# 8_U-FL-Connectors_no_GND.net
KiCad netlist of a schematic drawn in Altium Designer
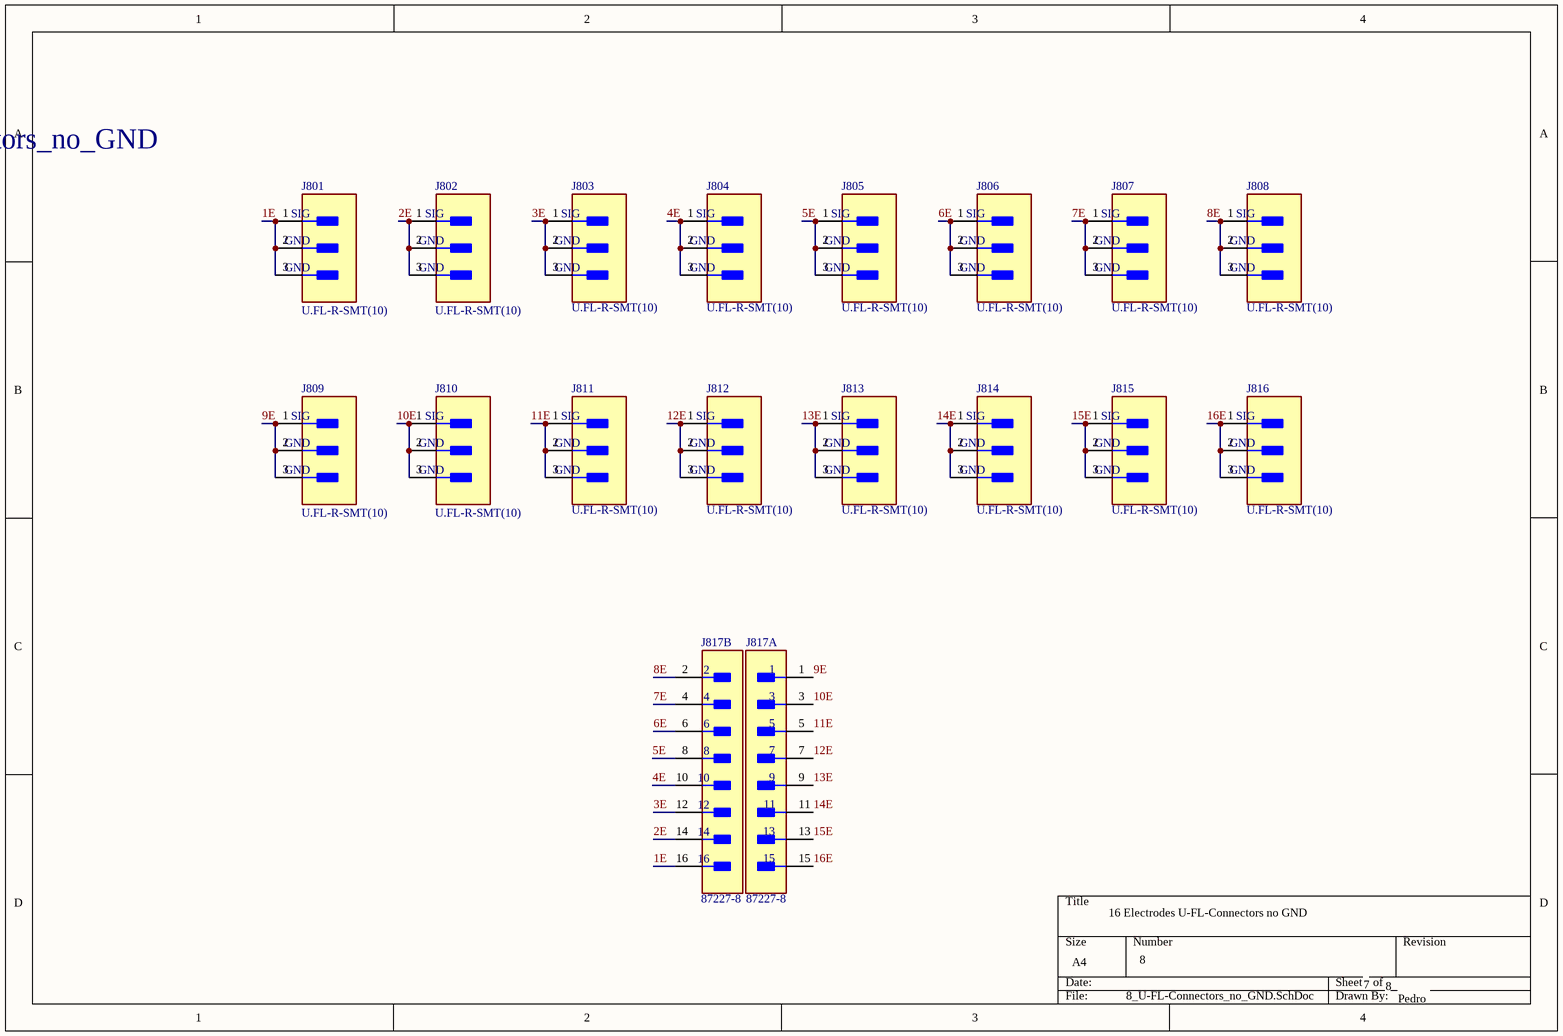
[diagram p0: 8_U-FL-Connectors_no_GND.SchDoc]

(export (version "E")
  (design (tool "Eeschema 10.0.6"))
  (components
    (comp (ref "J801")
      (value "U.FL-R-SMT(10)")
      (footprint "FP-U_FL-R-SMT_10-MFG")
      (description "CONN U.FL RCPT STR 50 OHM SMD")
      (libsource (lib "RPI_EIT_SchLib") (part "eef6fde44c591823e8076210edfe12f"))
    )
    (comp (ref "J802")
      (value "U.FL-R-SMT(10)")
      (footprint "FP-U_FL-R-SMT_10-MFG")
      (description "CONN U.FL RCPT STR 50 OHM SMD")
      (libsource (lib "RPI_EIT_SchLib") (part "eef6fde44c591823e8076210edfe12f"))
    )
    (comp (ref "J803")
      (value "U.FL-R-SMT(10)")
      (footprint "FP-U_FL-R-SMT_10-MFG")
      (description "CONN U.FL RCPT STR 50 OHM SMD")
      (libsource (lib "RPI_EIT_SchLib") (part "eef6fde44c591823e8076210edfe12f"))
    )
    (comp (ref "J804")
      (value "U.FL-R-SMT(10)")
      (footprint "FP-U_FL-R-SMT_10-MFG")
      (description "CONN U.FL RCPT STR 50 OHM SMD")
      (libsource (lib "RPI_EIT_SchLib") (part "eef6fde44c591823e8076210edfe12f"))
    )
    (comp (ref "J805")
      (value "U.FL-R-SMT(10)")
      (footprint "FP-U_FL-R-SMT_10-MFG")
      (description "CONN U.FL RCPT STR 50 OHM SMD")
      (libsource (lib "RPI_EIT_SchLib") (part "eef6fde44c591823e8076210edfe12f"))
    )
    (comp (ref "J806")
      (value "U.FL-R-SMT(10)")
      (footprint "FP-U_FL-R-SMT_10-MFG")
      (description "CONN U.FL RCPT STR 50 OHM SMD")
      (libsource (lib "RPI_EIT_SchLib") (part "eef6fde44c591823e8076210edfe12f"))
    )
    (comp (ref "J807")
      (value "U.FL-R-SMT(10)")
      (footprint "FP-U_FL-R-SMT_10-MFG")
      (description "CONN U.FL RCPT STR 50 OHM SMD")
      (libsource (lib "RPI_EIT_SchLib") (part "eef6fde44c591823e8076210edfe12f"))
    )
    (comp (ref "J808")
      (value "U.FL-R-SMT(10)")
      (footprint "FP-U_FL-R-SMT_10-MFG")
      (description "CONN U.FL RCPT STR 50 OHM SMD")
      (libsource (lib "RPI_EIT_SchLib") (part "eef6fde44c591823e8076210edfe12f"))
    )
    (comp (ref "J809")
      (value "U.FL-R-SMT(10)")
      (footprint "FP-U_FL-R-SMT_10-MFG")
      (description "CONN U.FL RCPT STR 50 OHM SMD")
      (libsource (lib "RPI_EIT_SchLib") (part "eef6fde44c591823e8076210edfe12f"))
    )
    (comp (ref "J810")
      (value "U.FL-R-SMT(10)")
      (footprint "FP-U_FL-R-SMT_10-MFG")
      (description "CONN U.FL RCPT STR 50 OHM SMD")
      (libsource (lib "RPI_EIT_SchLib") (part "eef6fde44c591823e8076210edfe12f"))
    )
    (comp (ref "J811")
      (value "U.FL-R-SMT(10)")
      (footprint "FP-U_FL-R-SMT_10-MFG")
      (description "CONN U.FL RCPT STR 50 OHM SMD")
      (libsource (lib "RPI_EIT_SchLib") (part "eef6fde44c591823e8076210edfe12f"))
    )
    (comp (ref "J812")
      (value "U.FL-R-SMT(10)")
      (footprint "FP-U_FL-R-SMT_10-MFG")
      (description "CONN U.FL RCPT STR 50 OHM SMD")
      (libsource (lib "RPI_EIT_SchLib") (part "eef6fde44c591823e8076210edfe12f"))
    )
    (comp (ref "J813")
      (value "U.FL-R-SMT(10)")
      (footprint "FP-U_FL-R-SMT_10-MFG")
      (description "CONN U.FL RCPT STR 50 OHM SMD")
      (libsource (lib "RPI_EIT_SchLib") (part "eef6fde44c591823e8076210edfe12f"))
    )
    (comp (ref "J814")
      (value "U.FL-R-SMT(10)")
      (footprint "FP-U_FL-R-SMT_10-MFG")
      (description "CONN U.FL RCPT STR 50 OHM SMD")
      (libsource (lib "RPI_EIT_SchLib") (part "eef6fde44c591823e8076210edfe12f"))
    )
    (comp (ref "J815")
      (value "U.FL-R-SMT(10)")
      (footprint "FP-U_FL-R-SMT_10-MFG")
      (description "CONN U.FL RCPT STR 50 OHM SMD")
      (libsource (lib "RPI_EIT_SchLib") (part "eef6fde44c591823e8076210edfe12f"))
    )
    (comp (ref "J816")
      (value "U.FL-R-SMT(10)")
      (footprint "FP-U_FL-R-SMT_10-MFG")
      (description "CONN U.FL RCPT STR 50 OHM SMD")
      (libsource (lib "RPI_EIT_SchLib") (part "eef6fde44c591823e8076210edfe12f"))
    )
    (comp (ref "J817")
      (value "87227-8")
      (footprint "FP-87227-8-MFG")
      (description "CONN HEADER VERT 16POS 2.54MM")
      (fields
        (field (name "MANUFACTURER") "TE Connectivity")
        (field (name "OCTOPART") "https://octopart.com/87227-8-te+connectivity-39407754")
      )
      (libsource (lib "") (part "4b6d22b45e2f925f038cba5d936fbcc_1"))
    )
  )
  (nets
    (net (code "1") (name "/1E") (class "Default")
      (node (ref "J801") (pin "1") (pinfunction "SIG_1") (pintype "passive"))
      (node (ref "J801") (pin "2") (pinfunction "GND_2") (pintype "power_in"))
      (node (ref "J801") (pin "3") (pinfunction "GND_3") (pintype "power_in"))
      (node (ref "J817") (pin "16") (pinfunction "16_16") (pintype "passive"))
    )
    (net (code "2") (name "/2E") (class "Default")
      (node (ref "J802") (pin "1") (pinfunction "SIG_1") (pintype "passive"))
      (node (ref "J802") (pin "2") (pinfunction "GND_2") (pintype "power_in"))
      (node (ref "J802") (pin "3") (pinfunction "GND_3") (pintype "power_in"))
      (node (ref "J817") (pin "14") (pinfunction "14_14") (pintype "passive"))
    )
    (net (code "3") (name "/3E") (class "Default")
      (node (ref "J803") (pin "1") (pinfunction "SIG_1") (pintype "passive"))
      (node (ref "J803") (pin "2") (pinfunction "GND_2") (pintype "power_in"))
      (node (ref "J803") (pin "3") (pinfunction "GND_3") (pintype "power_in"))
      (node (ref "J817") (pin "12") (pinfunction "12_12") (pintype "passive"))
    )
    (net (code "4") (name "/4E") (class "Default")
      (node (ref "J804") (pin "1") (pinfunction "SIG_1") (pintype "passive"))
      (node (ref "J804") (pin "2") (pinfunction "GND_2") (pintype "power_in"))
      (node (ref "J804") (pin "3") (pinfunction "GND_3") (pintype "power_in"))
      (node (ref "J817") (pin "10") (pinfunction "10_10") (pintype "passive"))
    )
    (net (code "5") (name "/5E") (class "Default")
      (node (ref "J805") (pin "1") (pinfunction "SIG_1") (pintype "passive"))
      (node (ref "J805") (pin "2") (pinfunction "GND_2") (pintype "power_in"))
      (node (ref "J805") (pin "3") (pinfunction "GND_3") (pintype "power_in"))
      (node (ref "J817") (pin "8") (pinfunction "8_8") (pintype "passive"))
    )
    (net (code "6") (name "/6E") (class "Default")
      (node (ref "J806") (pin "1") (pinfunction "SIG_1") (pintype "passive"))
      (node (ref "J806") (pin "2") (pinfunction "GND_2") (pintype "power_in"))
      (node (ref "J806") (pin "3") (pinfunction "GND_3") (pintype "power_in"))
      (node (ref "J817") (pin "6") (pinfunction "6_6") (pintype "passive"))
    )
    (net (code "7") (name "/7E") (class "Default")
      (node (ref "J807") (pin "1") (pinfunction "SIG_1") (pintype "passive"))
      (node (ref "J807") (pin "2") (pinfunction "GND_2") (pintype "power_in"))
      (node (ref "J807") (pin "3") (pinfunction "GND_3") (pintype "power_in"))
      (node (ref "J817") (pin "4") (pinfunction "4_4") (pintype "passive"))
    )
    (net (code "8") (name "/8E") (class "Default")
      (node (ref "J808") (pin "1") (pinfunction "SIG_1") (pintype "passive"))
      (node (ref "J808") (pin "2") (pinfunction "GND_2") (pintype "power_in"))
      (node (ref "J808") (pin "3") (pinfunction "GND_3") (pintype "power_in"))
      (node (ref "J817") (pin "2") (pinfunction "2_2") (pintype "passive"))
    )
    (net (code "9") (name "/9E") (class "Default")
      (node (ref "J809") (pin "1") (pinfunction "SIG_1") (pintype "passive"))
      (node (ref "J809") (pin "2") (pinfunction "GND_2") (pintype "power_in"))
      (node (ref "J809") (pin "3") (pinfunction "GND_3") (pintype "power_in"))
      (node (ref "J817") (pin "1") (pinfunction "1_1") (pintype "passive"))
    )
    (net (code "10") (name "/10E") (class "Default")
      (node (ref "J810") (pin "1") (pinfunction "SIG_1") (pintype "passive"))
      (node (ref "J810") (pin "2") (pinfunction "GND_2") (pintype "power_in"))
      (node (ref "J810") (pin "3") (pinfunction "GND_3") (pintype "power_in"))
      (node (ref "J817") (pin "3") (pinfunction "3_3") (pintype "passive"))
    )
    (net (code "11") (name "/11E") (class "Default")
      (node (ref "J811") (pin "1") (pinfunction "SIG_1") (pintype "passive"))
      (node (ref "J811") (pin "2") (pinfunction "GND_2") (pintype "power_in"))
      (node (ref "J811") (pin "3") (pinfunction "GND_3") (pintype "power_in"))
      (node (ref "J817") (pin "5") (pinfunction "5_5") (pintype "passive"))
    )
    (net (code "12") (name "/12E") (class "Default")
      (node (ref "J812") (pin "1") (pinfunction "SIG_1") (pintype "passive"))
      (node (ref "J812") (pin "2") (pinfunction "GND_2") (pintype "power_in"))
      (node (ref "J812") (pin "3") (pinfunction "GND_3") (pintype "power_in"))
      (node (ref "J817") (pin "7") (pinfunction "7_7") (pintype "passive"))
    )
    (net (code "13") (name "/13E") (class "Default")
      (node (ref "J813") (pin "1") (pinfunction "SIG_1") (pintype "passive"))
      (node (ref "J813") (pin "2") (pinfunction "GND_2") (pintype "power_in"))
      (node (ref "J813") (pin "3") (pinfunction "GND_3") (pintype "power_in"))
      (node (ref "J817") (pin "9") (pinfunction "9_9") (pintype "passive"))
    )
    (net (code "14") (name "/14E") (class "Default")
      (node (ref "J814") (pin "1") (pinfunction "SIG_1") (pintype "passive"))
      (node (ref "J814") (pin "2") (pinfunction "GND_2") (pintype "power_in"))
      (node (ref "J814") (pin "3") (pinfunction "GND_3") (pintype "power_in"))
      (node (ref "J817") (pin "11") (pinfunction "11_11") (pintype "passive"))
    )
    (net (code "15") (name "/15E") (class "Default")
      (node (ref "J815") (pin "1") (pinfunction "SIG_1") (pintype "passive"))
      (node (ref "J815") (pin "2") (pinfunction "GND_2") (pintype "power_in"))
      (node (ref "J815") (pin "3") (pinfunction "GND_3") (pintype "power_in"))
      (node (ref "J817") (pin "13") (pinfunction "13_13") (pintype "passive"))
    )
    (net (code "16") (name "/16E") (class "Default")
      (node (ref "J816") (pin "1") (pinfunction "SIG_1") (pintype "passive"))
      (node (ref "J816") (pin "2") (pinfunction "GND_2") (pintype "power_in"))
      (node (ref "J816") (pin "3") (pinfunction "GND_3") (pintype "power_in"))
      (node (ref "J817") (pin "15") (pinfunction "15_15") (pintype "passive"))
    )
  )
)
